# Ethernet.net
KiCad netlist of a schematic drawn in Altium Designer
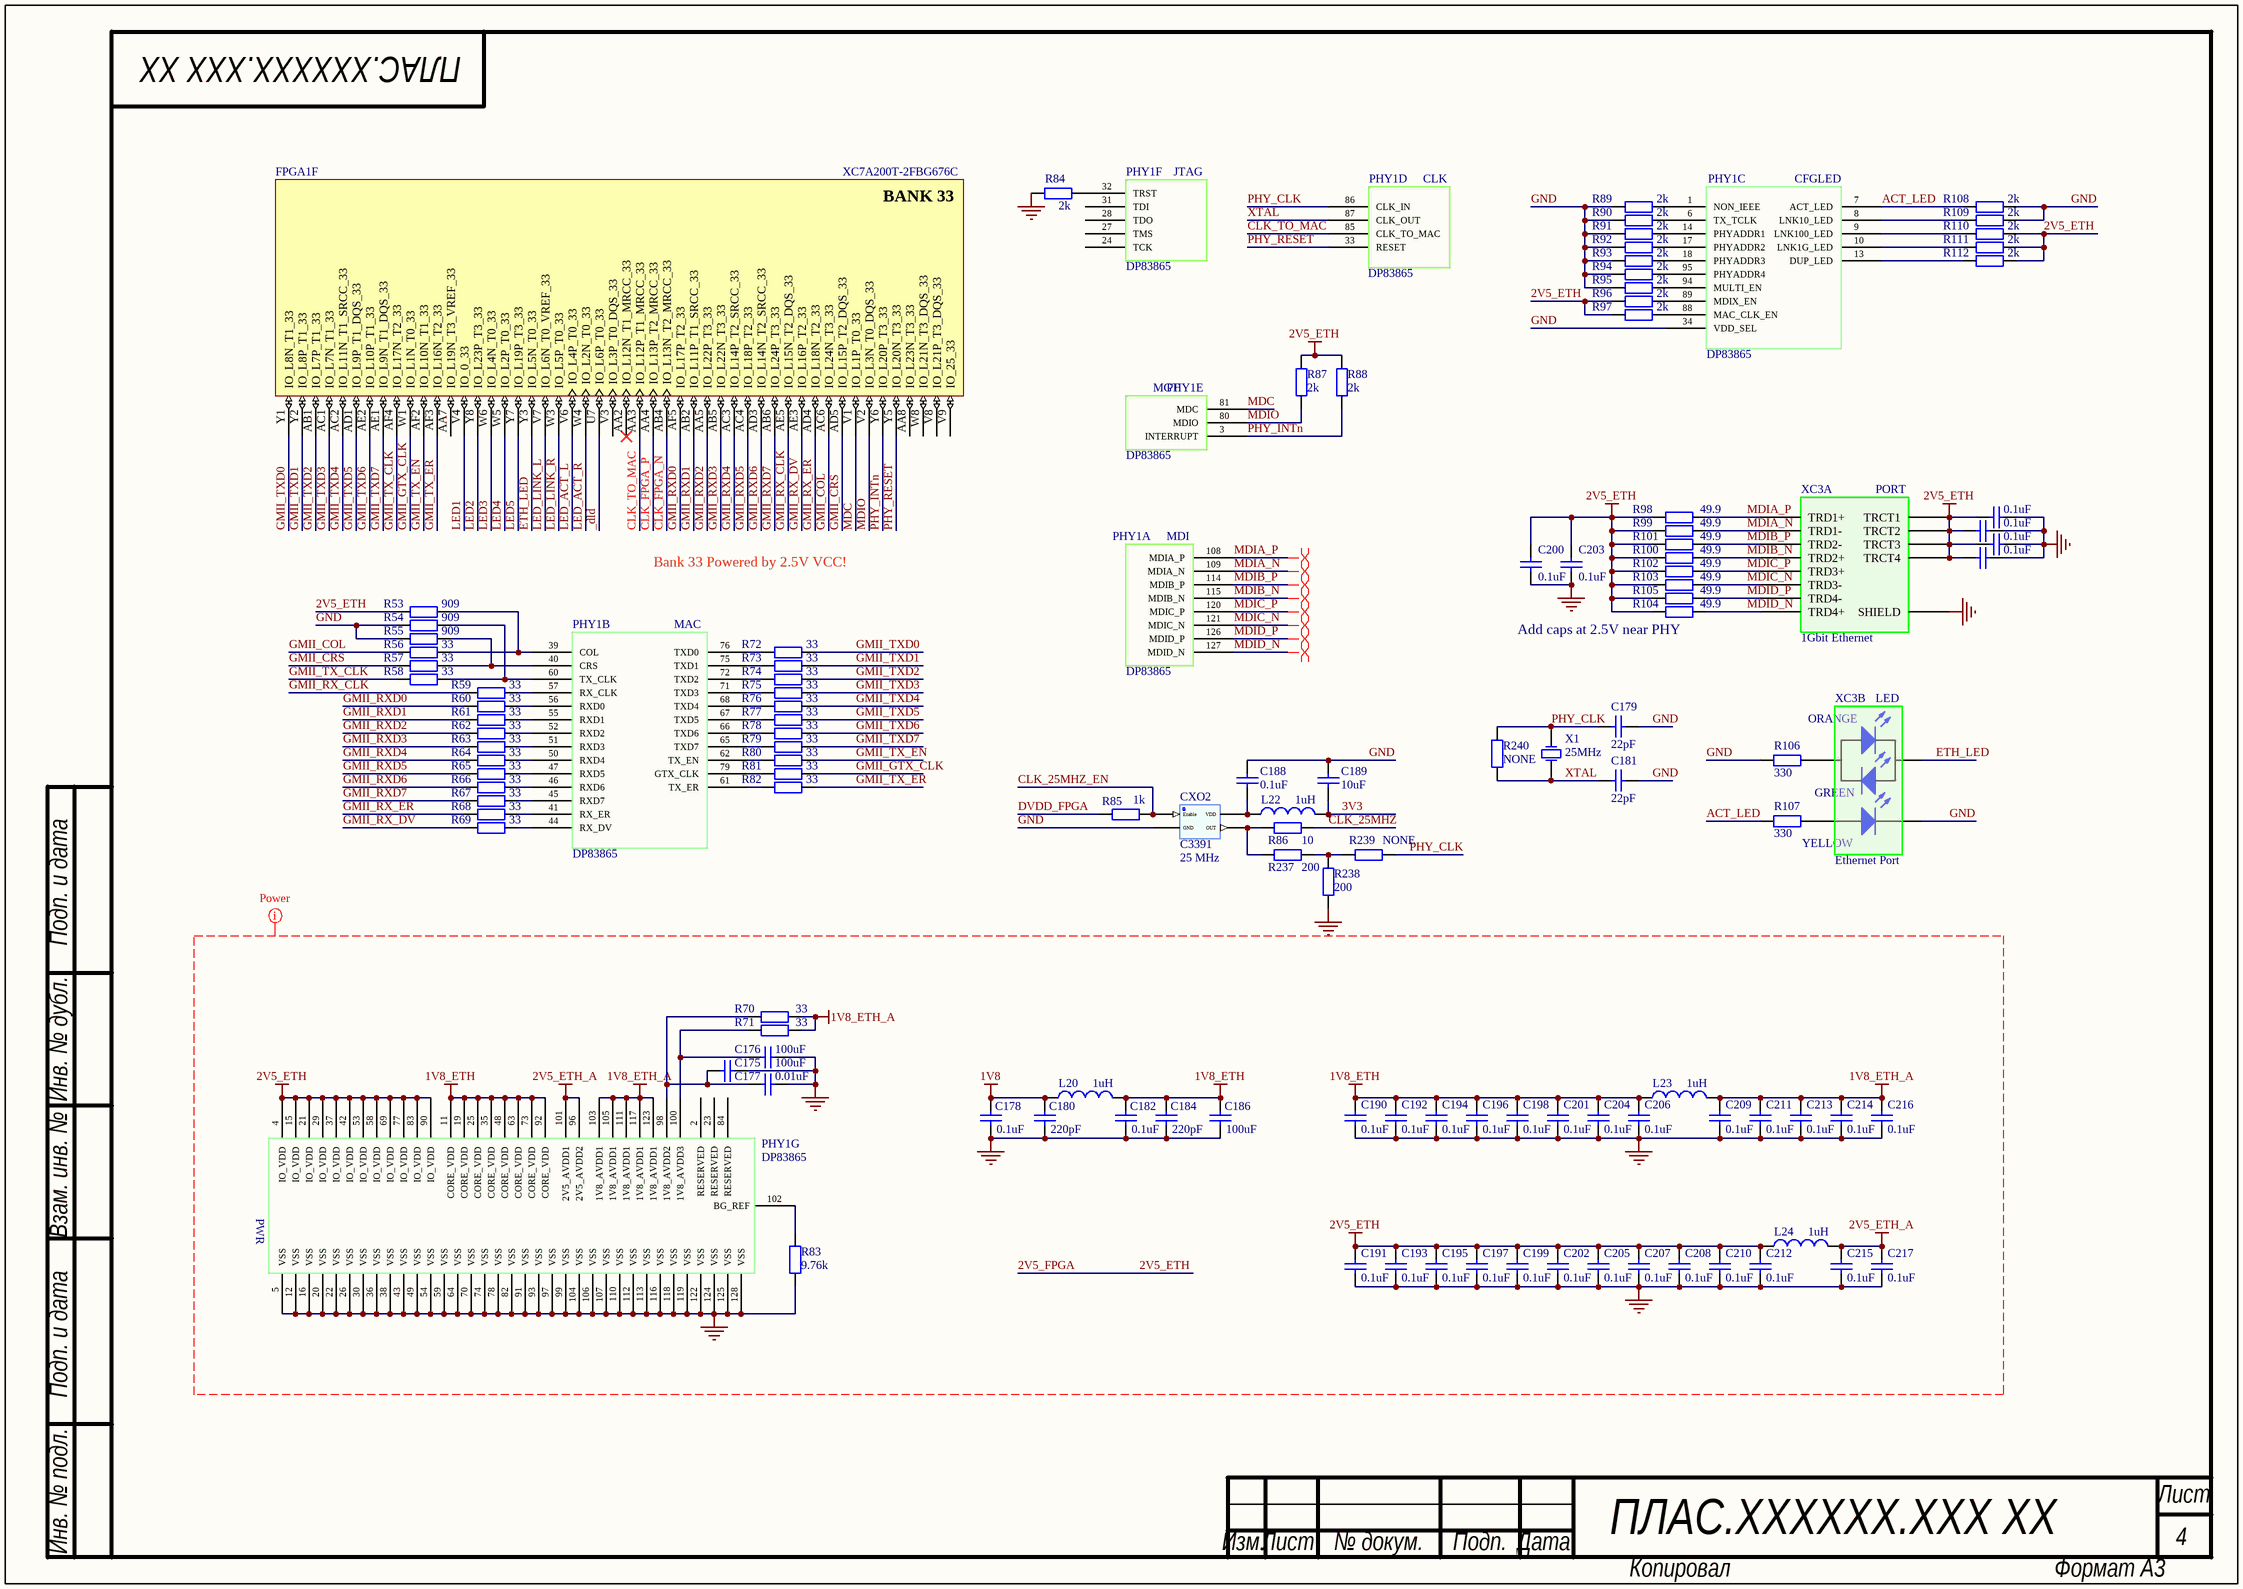
[diagram p0: Ethernet.SchDoc]

(export (version "E")
  (design (tool "Eeschema 10.0.6"))
  (components
    (comp (ref "C175")
      (value "100uF")
      (footprint "C1210")
      (description "Cer Cap Large")
      (fields (field (name "MANUFACTURER") "Murata") (field (name "TOLERANCE") "20%"))
      (libsource (lib "USRP2_Clone") (part "Cap uF"))
    )
    (comp (ref "C176")
      (value "100uF")
      (footprint "C1210")
      (description "Cer Cap Large")
      (fields (field (name "MANUFACTURER") "Murata") (field (name "TOLERANCE") "20%"))
      (libsource (lib "USRP2_Clone") (part "Cap uF"))
    )
    (comp (ref "C177")
      (value "0.01uF")
      (footprint "C0603")
      (description "Cer Cap Small")
      (fields (field (name "MANUFACTURER") "Murata") (field (name "VOLTAGE") "50V"))
      (libsource (lib "") (part "Cer Cap_1"))
    )
    (comp (ref "C178")
      (value "0.1uF")
      (footprint "C0603")
      (description "Cer Cap Small")
      (fields (field (name "MANUFACTURER") "Murata") (field (name "VOLTAGE") "16V"))
      (libsource (lib "USRP2_Clone") (part "Cer Cap"))
    )
    (comp (ref "C179")
      (value "22pF")
      (footprint "С0402")
      (description "Cer Cap Small")
      (fields (field (name "MANUFACTURER") "Murata") (field (name "VOLTAGE") "50V"))
      (libsource (lib "USRP2_Clone") (part "Cer Cap"))
    )
    (comp (ref "C180")
      (value "220pF")
      (footprint "C0603")
      (description "Cer Cap Small")
      (fields (field (name "MANUFACTURER") "Murata") (field (name "VOLTAGE") "16V"))
      (libsource (lib "USRP2_Clone") (part "Cer Cap"))
    )
    (comp (ref "C181")
      (value "22pF")
      (footprint "С0402")
      (description "Cer Cap Small")
      (fields (field (name "MANUFACTURER") "Murata") (field (name "VOLTAGE") "50V"))
      (libsource (lib "USRP2_Clone") (part "Cer Cap"))
    )
    (comp (ref "C182")
      (value "0.1uF")
      (footprint "C0603")
      (description "Cer Cap Small")
      (fields (field (name "MANUFACTURER") "Murata") (field (name "VOLTAGE") "16V"))
      (libsource (lib "USRP2_Clone") (part "Cer Cap"))
    )
    (comp (ref "C184")
      (value "220pF")
      (footprint "C0603")
      (description "Cer Cap Small")
      (fields (field (name "MANUFACTURER") "Murata") (field (name "VOLTAGE") "16V"))
      (libsource (lib "USRP2_Clone") (part "Cer Cap"))
    )
    (comp (ref "C186")
      (value "100uF")
      (footprint "C1210")
      (description "Cer Cap Large")
      (fields (field (name "MANUFACTURER") "Murata") (field (name "TOLERANCE") "20%"))
      (libsource (lib "") (part "Cap uF_1"))
    )
    (comp (ref "C188")
      (value "0.1uF")
      (footprint "C0603")
      (description "Cer Cap Small")
      (fields (field (name "MANUFACTURER") "Murata") (field (name "VOLTAGE") "16V"))
      (libsource (lib "") (part "Cer Cap_1"))
    )
    (comp (ref "C189")
      (value "10uF")
      (footprint "C0603")
      (description "Cer Cap Small")
      (fields (field (name "MANUFACTURER") "Murata") (field (name "VOLTAGE") "6.3V"))
      (libsource (lib "") (part "Cer Cap_1"))
    )
    (comp (ref "C190")
      (value "0.1uF")
      (footprint "C0603")
      (description "Cer Cap Small")
      (fields (field (name "MANUFACTURER") "Murata") (field (name "VOLTAGE") "16V"))
      (libsource (lib "") (part "Cer Cap_1"))
    )
    (comp (ref "C191")
      (value "0.1uF")
      (footprint "C0603")
      (description "Cer Cap Small")
      (fields (field (name "MANUFACTURER") "Murata") (field (name "VOLTAGE") "16V"))
      (libsource (lib "USRP2_Clone") (part "Cer Cap"))
    )
    (comp (ref "C192")
      (value "0.1uF")
      (footprint "C0603")
      (description "Cer Cap Small")
      (fields (field (name "MANUFACTURER") "Murata") (field (name "VOLTAGE") "16V"))
      (libsource (lib "USRP2_Clone") (part "Cer Cap"))
    )
    (comp (ref "C193")
      (value "0.1uF")
      (footprint "C0603")
      (description "Cer Cap Small")
      (fields (field (name "MANUFACTURER") "Murata") (field (name "VOLTAGE") "16V"))
      (libsource (lib "USRP2_Clone") (part "Cer Cap"))
    )
    (comp (ref "C194")
      (value "0.1uF")
      (footprint "C0603")
      (description "Cer Cap Small")
      (fields (field (name "MANUFACTURER") "Murata") (field (name "VOLTAGE") "16V"))
      (libsource (lib "USRP2_Clone") (part "Cer Cap"))
    )
    (comp (ref "C195")
      (value "0.1uF")
      (footprint "C0603")
      (description "Cer Cap Small")
      (fields (field (name "MANUFACTURER") "Murata") (field (name "VOLTAGE") "16V"))
      (libsource (lib "USRP2_Clone") (part "Cer Cap"))
    )
    (comp (ref "C196")
      (value "0.1uF")
      (footprint "C0603")
      (description "Cer Cap Small")
      (fields (field (name "MANUFACTURER") "Murata") (field (name "VOLTAGE") "16V"))
      (libsource (lib "") (part "Cer Cap_1"))
    )
    (comp (ref "C197")
      (value "0.1uF")
      (footprint "C0603")
      (description "Cer Cap Small")
      (fields (field (name "MANUFACTURER") "Murata") (field (name "VOLTAGE") "16V"))
      (libsource (lib "USRP2_Clone") (part "Cer Cap"))
    )
    (comp (ref "C198")
      (value "0.1uF")
      (footprint "C0603")
      (description "Cer Cap Small")
      (fields (field (name "MANUFACTURER") "Murata") (field (name "VOLTAGE") "16V"))
      (libsource (lib "USRP2_Clone") (part "Cer Cap"))
    )
    (comp (ref "C199")
      (value "0.1uF")
      (footprint "C0603")
      (description "Cer Cap Small")
      (fields (field (name "MANUFACTURER") "Murata") (field (name "VOLTAGE") "16V"))
      (libsource (lib "") (part "Cer Cap_1"))
    )
    (comp (ref "C200")
      (value "0.1uF")
      (footprint "С0402")
      (description "Cer Cap Small")
      (fields (field (name "MANUFACTURER") "Murata") (field (name "VOLTAGE") "16V"))
      (libsource (lib "") (part "Cer Cap_1"))
    )
    (comp (ref "C201")
      (value "0.1uF")
      (footprint "C0603")
      (description "Cer Cap Small")
      (fields (field (name "MANUFACTURER") "Murata") (field (name "VOLTAGE") "16V"))
      (libsource (lib "USRP2_Clone") (part "Cer Cap"))
    )
    (comp (ref "C202")
      (value "0.1uF")
      (footprint "C0603")
      (description "Cer Cap Small")
      (fields (field (name "MANUFACTURER") "Murata") (field (name "VOLTAGE") "16V"))
      (libsource (lib "") (part "Cer Cap_1"))
    )
    (comp (ref "C203")
      (value "0.1uF")
      (footprint "С0402")
      (description "Cer Cap Small")
      (fields (field (name "MANUFACTURER") "Murata") (field (name "VOLTAGE") "16V"))
      (libsource (lib "") (part "Cer Cap_1"))
    )
    (comp (ref "C204")
      (value "0.1uF")
      (footprint "C0603")
      (description "Cer Cap Small")
      (fields (field (name "MANUFACTURER") "Murata") (field (name "VOLTAGE") "16V"))
      (libsource (lib "USRP2_Clone") (part "Cer Cap"))
    )
    (comp (ref "C205")
      (value "0.1uF")
      (footprint "C0603")
      (description "Cer Cap Small")
      (fields (field (name "MANUFACTURER") "Murata") (field (name "VOLTAGE") "16V"))
      (libsource (lib "USRP2_Clone") (part "Cer Cap"))
    )
    (comp (ref "C206")
      (value "0.1uF")
      (footprint "C0603")
      (description "Cer Cap Small")
      (fields (field (name "MANUFACTURER") "Murata") (field (name "VOLTAGE") "16V"))
      (libsource (lib "USRP2_Clone") (part "Cer Cap"))
    )
    (comp (ref "C207")
      (value "0.1uF")
      (footprint "C0603")
      (description "Cer Cap Small")
      (fields (field (name "MANUFACTURER") "Murata") (field (name "VOLTAGE") "16V"))
      (libsource (lib "USRP2_Clone") (part "Cer Cap"))
    )
    (comp (ref "C208")
      (value "0.1uF")
      (footprint "C0603")
      (description "Cer Cap Small")
      (fields (field (name "MANUFACTURER") "Murata") (field (name "VOLTAGE") "16V"))
      (libsource (lib "USRP2_Clone") (part "Cer Cap"))
    )
    (comp (ref "C209")
      (value "0.1uF")
      (footprint "C0603")
      (description "Cer Cap Small")
      (fields (field (name "MANUFACTURER") "Murata") (field (name "VOLTAGE") "16V"))
      (libsource (lib "USRP2_Clone") (part "Cer Cap"))
    )
    (comp (ref "C210")
      (value "0.1uF")
      (footprint "C0603")
      (description "Cer Cap Small")
      (fields (field (name "MANUFACTURER") "Murata") (field (name "VOLTAGE") "16V"))
      (libsource (lib "USRP2_Clone") (part "Cer Cap"))
    )
    (comp (ref "C211")
      (value "0.1uF")
      (footprint "C0603")
      (description "Cer Cap Small")
      (fields (field (name "MANUFACTURER") "Murata") (field (name "VOLTAGE") "16V"))
      (libsource (lib "USRP2_Clone") (part "Cer Cap"))
    )
    (comp (ref "C212")
      (value "0.1uF")
      (footprint "C0603")
      (description "Cer Cap Small")
      (fields (field (name "MANUFACTURER") "Murata") (field (name "VOLTAGE") "16V"))
      (libsource (lib "USRP2_Clone") (part "Cer Cap"))
    )
    (comp (ref "C213")
      (value "0.1uF")
      (footprint "C0603")
      (description "Cer Cap Small")
      (fields (field (name "MANUFACTURER") "Murata") (field (name "VOLTAGE") "16V"))
      (libsource (lib "USRP2_Clone") (part "Cer Cap"))
    )
    (comp (ref "C214")
      (value "0.1uF")
      (footprint "C0603")
      (description "Cer Cap Small")
      (fields (field (name "MANUFACTURER") "Murata") (field (name "VOLTAGE") "16V"))
      (libsource (lib "USRP2_Clone") (part "Cer Cap"))
    )
    (comp (ref "C215")
      (value "0.1uF")
      (footprint "C0603")
      (description "Cer Cap Small")
      (fields (field (name "MANUFACTURER") "Murata") (field (name "VOLTAGE") "16V"))
      (libsource (lib "USRP2_Clone") (part "Cer Cap"))
    )
    (comp (ref "C216")
      (value "0.1uF")
      (footprint "C0603")
      (description "Cer Cap Small")
      (fields (field (name "MANUFACTURER") "Murata") (field (name "VOLTAGE") "16V"))
      (libsource (lib "USRP2_Clone") (part "Cer Cap"))
    )
    (comp (ref "C217")
      (value "0.1uF")
      (footprint "C0603")
      (description "Cer Cap Small")
      (fields (field (name "MANUFACTURER") "Murata") (field (name "VOLTAGE") "16V"))
      (libsource (lib "USRP2_Clone") (part "Cer Cap"))
    )
    (comp (ref "C218")
      (value "0.1uF")
      (footprint "С0402")
      (description "Cer Cap Small")
      (fields (field (name "MANUFACTURER") "Murata") (field (name "VOLTAGE") "50V"))
      (libsource (lib "USRP2_Clone") (part "Cer Cap"))
    )
    (comp (ref "C219")
      (value "0.1uF")
      (footprint "С0402")
      (description "Cer Cap Small")
      (fields (field (name "MANUFACTURER") "Murata") (field (name "VOLTAGE") "50V"))
      (libsource (lib "") (part "Cer Cap_1"))
    )
    (comp (ref "C220")
      (value "0.1uF")
      (footprint "С0402")
      (description "Cer Cap Small")
      (fields (field (name "MANUFACTURER") "Murata") (field (name "VOLTAGE") "50V"))
      (libsource (lib "USRP2_Clone") (part "Cer Cap"))
    )
    (comp (ref "C221")
      (value "0.1uF")
      (footprint "С0402")
      (description "Cer Cap Small")
      (fields (field (name "MANUFACTURER") "Murata") (field (name "VOLTAGE") "50V"))
      (libsource (lib "USRP2_Clone") (part "Cer Cap"))
    )
    (comp (ref "CXO2")
      (value "C3391")
      (footprint "CTS_CB3")
      (description "Crystal Oscillator")
      (fields
        (field (name "VOLTAGE") "3.3V ±0.3V")
        (field (name "MANUFACTURER") "Crystek")
        (field (name "FREQUENCY") "25 MHz")
      )
      (libsource (lib "USRP2_Clone") (part "5x7 CXO"))
    )
    (comp (ref "FPGA1")
      (value "XC7A200T-2FBG676C")
      (footprint "FGG676")
      (description "Artix-7 FPGA, 400 User I/Os, 8 GTP, 676-Ball BGA, Speed Grade 2, Commercial Grade, Pb-Free")
      (fields (field (name "GENERIC PART NUMBER") "XC7A200T") (field (name "MANUFACTURER") "Xilinx"))
      (libsource (lib "USRP2_Clone") (part "XC7A200T-2FBG676C"))
    )
    (comp (ref "L20")
      (value "1uH")
      (footprint "L1210_Murata LQH")
      (description "Inductor_Power_Lines")
      (fields (field (name "TOLERANCE") "5%") (field (name "MANUFACTURER") "Murata"))
      (libsource (lib "") (part "Inductor_LF_1"))
    )
    (comp (ref "L22")
      (value "1uH")
      (footprint "L1206_Murata")
      (description "Inductor_Power_Lines")
      (fields (field (name "TOLERANCE") "5%") (field (name "MANUFACTURER") "Murata"))
      (libsource (lib "") (part "Inductor_LF_1"))
    )
    (comp (ref "L23")
      (value "1uH")
      (footprint "L1210_Murata LQH")
      (description "Inductor_Power_Lines")
      (fields (field (name "TOLERANCE") "5%") (field (name "MANUFACTURER") "Murata"))
      (libsource (lib "USRP2_Clone") (part "Inductor_LF"))
    )
    (comp (ref "L24")
      (value "1uH")
      (footprint "L1210_Murata LQH")
      (description "Inductor_Power_Lines")
      (fields (field (name "TOLERANCE") "5%") (field (name "MANUFACTURER") "Murata"))
      (libsource (lib "USRP2_Clone") (part "Inductor_LF"))
    )
    (comp (ref "PHY1")
      (value "DP83865")
      (footprint "LQFP-128")
      (description "10/100/1000 Ethernet Physical Layer")
      (libsource (lib "USRP2_Clone") (part "DP83865"))
    )
    (comp (ref "R53")
      (value "909")
      (footprint "R0402")
      (description "Resistor")
      (fields (field (name "TOLERANCE") "5%") (field (name "POWER") "0.062 Wt"))
      (libsource (lib "") (part "Res_1"))
    )
    (comp (ref "R54")
      (value "909")
      (footprint "R0402")
      (description "Resistor")
      (fields (field (name "TOLERANCE") "5%") (field (name "POWER") "0.062 Wt"))
      (libsource (lib "") (part "Res_1"))
    )
    (comp (ref "R55")
      (value "909")
      (footprint "R0402")
      (description "Resistor")
      (fields (field (name "TOLERANCE") "5%") (field (name "POWER") "0.062 Wt"))
      (libsource (lib "") (part "Res_2"))
    )
    (comp (ref "R56")
      (value "33")
      (footprint "R0402")
      (description "Resistor")
      (fields (field (name "TOLERANCE") "5%") (field (name "POWER") "0.062 Wt"))
      (libsource (lib "") (part "Res_1"))
    )
    (comp (ref "R57")
      (value "33")
      (footprint "R0402")
      (description "Resistor")
      (fields (field (name "TOLERANCE") "5%") (field (name "POWER") "0.062 Wt"))
      (libsource (lib "") (part "Res_1"))
    )
    (comp (ref "R58")
      (value "33")
      (footprint "R0402")
      (description "Resistor")
      (fields (field (name "TOLERANCE") "5%") (field (name "POWER") "0.062 Wt"))
      (libsource (lib "") (part "Res_1"))
    )
    (comp (ref "R59")
      (value "33")
      (footprint "R0402")
      (description "Resistor")
      (fields (field (name "TOLERANCE") "5%") (field (name "POWER") "0.062 Wt"))
      (libsource (lib "") (part "Res_2"))
    )
    (comp (ref "R60")
      (value "33")
      (footprint "R0402")
      (description "Resistor")
      (fields (field (name "TOLERANCE") "5%") (field (name "POWER") "0.062 Wt"))
      (libsource (lib "") (part "Res_2"))
    )
    (comp (ref "R61")
      (value "33")
      (footprint "R0402")
      (description "Resistor")
      (fields (field (name "TOLERANCE") "5%") (field (name "POWER") "0.062 Wt"))
      (libsource (lib "") (part "Res_2"))
    )
    (comp (ref "R62")
      (value "33")
      (footprint "R0402")
      (description "Resistor")
      (fields (field (name "TOLERANCE") "5%") (field (name "POWER") "0.062 Wt"))
      (libsource (lib "") (part "Res_2"))
    )
    (comp (ref "R63")
      (value "33")
      (footprint "R0402")
      (description "Resistor")
      (fields (field (name "TOLERANCE") "5%") (field (name "POWER") "0.062 Wt"))
      (libsource (lib "") (part "Res_2"))
    )
    (comp (ref "R64")
      (value "33")
      (footprint "R0402")
      (description "Resistor")
      (fields (field (name "TOLERANCE") "5%") (field (name "POWER") "0.062 Wt"))
      (libsource (lib "") (part "Res_2"))
    )
    (comp (ref "R65")
      (value "33")
      (footprint "R0402")
      (description "Resistor")
      (fields (field (name "TOLERANCE") "5%") (field (name "POWER") "0.062 Wt"))
      (libsource (lib "") (part "Res_2"))
    )
    (comp (ref "R66")
      (value "33")
      (footprint "R0402")
      (description "Resistor")
      (fields (field (name "TOLERANCE") "5%") (field (name "POWER") "0.062 Wt"))
      (libsource (lib "") (part "Res_2"))
    )
    (comp (ref "R67")
      (value "33")
      (footprint "R0402")
      (description "Resistor")
      (fields (field (name "TOLERANCE") "5%") (field (name "POWER") "0.062 Wt"))
      (libsource (lib "") (part "Res_2"))
    )
    (comp (ref "R68")
      (value "33")
      (footprint "R0402")
      (description "Resistor")
      (fields (field (name "TOLERANCE") "5%") (field (name "POWER") "0.062 Wt"))
      (libsource (lib "") (part "Res_2"))
    )
    (comp (ref "R69")
      (value "33")
      (footprint "R0402")
      (description "Resistor")
      (fields (field (name "TOLERANCE") "5%") (field (name "POWER") "0.062 Wt"))
      (libsource (lib "") (part "Res_2"))
    )
    (comp (ref "R70")
      (value "33")
      (footprint "R0402")
      (description "Resistor")
      (fields (field (name "TOLERANCE") "5%") (field (name "POWER") "0.062 Wt"))
      (libsource (lib "USRP2_Clone") (part "Res"))
    )
    (comp (ref "R71")
      (value "33")
      (footprint "R0402")
      (description "Resistor")
      (fields (field (name "TOLERANCE") "5%") (field (name "POWER") "0.062 Wt"))
      (libsource (lib "USRP2_Clone") (part "Res"))
    )
    (comp (ref "R72")
      (value "33")
      (footprint "R0402")
      (description "Resistor")
      (fields (field (name "TOLERANCE") "5%") (field (name "POWER") "0.062 Wt"))
      (libsource (lib "") (part "Res_1"))
    )
    (comp (ref "R73")
      (value "33")
      (footprint "R0402")
      (description "Resistor")
      (fields (field (name "TOLERANCE") "5%") (field (name "POWER") "0.062 Wt"))
      (libsource (lib "") (part "Res_1"))
    )
    (comp (ref "R74")
      (value "33")
      (footprint "R0402")
      (description "Resistor")
      (fields (field (name "TOLERANCE") "5%") (field (name "POWER") "0.062 Wt"))
      (libsource (lib "") (part "Res_1"))
    )
    (comp (ref "R75")
      (value "33")
      (footprint "R0402")
      (description "Resistor")
      (fields (field (name "TOLERANCE") "5%") (field (name "POWER") "0.062 Wt"))
      (libsource (lib "") (part "Res_1"))
    )
    (comp (ref "R76")
      (value "33")
      (footprint "R0402")
      (description "Resistor")
      (fields (field (name "TOLERANCE") "5%") (field (name "POWER") "0.062 Wt"))
      (libsource (lib "") (part "Res_1"))
    )
    (comp (ref "R77")
      (value "33")
      (footprint "R0402")
      (description "Resistor")
      (fields (field (name "TOLERANCE") "5%") (field (name "POWER") "0.062 Wt"))
      (libsource (lib "") (part "Res_1"))
    )
    (comp (ref "R78")
      (value "33")
      (footprint "R0402")
      (description "Resistor")
      (fields (field (name "TOLERANCE") "5%") (field (name "POWER") "0.062 Wt"))
      (libsource (lib "") (part "Res_1"))
    )
    (comp (ref "R79")
      (value "33")
      (footprint "R0402")
      (description "Resistor")
      (fields (field (name "TOLERANCE") "5%") (field (name "POWER") "0.062 Wt"))
      (libsource (lib "") (part "Res_1"))
    )
    (comp (ref "R80")
      (value "33")
      (footprint "R0402")
      (description "Resistor")
      (fields (field (name "TOLERANCE") "5%") (field (name "POWER") "0.062 Wt"))
      (libsource (lib "") (part "Res_1"))
    )
    (comp (ref "R81")
      (value "33")
      (footprint "R0402")
      (description "Resistor")
      (fields (field (name "TOLERANCE") "5%") (field (name "POWER") "0.062 Wt"))
      (libsource (lib "") (part "Res_1"))
    )
    (comp (ref "R82")
      (value "33")
      (footprint "R0402")
      (description "Resistor")
      (fields (field (name "TOLERANCE") "5%") (field (name "POWER") "0.062 Wt"))
      (libsource (lib "") (part "Res_1"))
    )
    (comp (ref "R83")
      (value "9.76k")
      (footprint "R0402")
      (description "Resistor")
      (fields (field (name "TOLERANCE") "5%") (field (name "POWER") "0.062 Wt"))
      (libsource (lib "") (part "Res_4"))
    )
    (comp (ref "R84")
      (value "2k")
      (footprint "R0402")
      (description "Resistor")
      (fields (field (name "TOLERANCE") "5%") (field (name "POWER") "0.062 Wt"))
      (libsource (lib "") (part "Res_2"))
    )
    (comp (ref "R85")
      (value "1k")
      (footprint "R0402")
      (description "Resistor")
      (fields (field (name "TOLERANCE") "5%") (field (name "POWER") "0.062 Wt"))
      (libsource (lib "") (part "Res_2"))
    )
    (comp (ref "R86")
      (value "10")
      (footprint "R0402")
      (description "Resistor")
      (fields (field (name "TOLERANCE") "5%") (field (name "POWER") "0.062 Wt"))
      (libsource (lib "") (part "Res_2"))
    )
    (comp (ref "R87")
      (value "2k")
      (footprint "R0402")
      (description "Resistor")
      (fields (field (name "TOLERANCE") "5%") (field (name "POWER") "0.062 Wt"))
      (libsource (lib "") (part "Res_3"))
    )
    (comp (ref "R88")
      (value "2k")
      (footprint "R0402")
      (description "Resistor")
      (fields (field (name "TOLERANCE") "5%") (field (name "POWER") "0.062 Wt"))
      (libsource (lib "USRP2_Clone") (part "Res"))
    )
    (comp (ref "R89")
      (value "2k")
      (footprint "R0402")
      (description "Resistor")
      (fields (field (name "TOLERANCE") "5%") (field (name "POWER") "0.062 Wt"))
      (libsource (lib "") (part "Res_2"))
    )
    (comp (ref "R90")
      (value "2k")
      (footprint "R0402")
      (description "Resistor")
      (fields (field (name "TOLERANCE") "5%") (field (name "POWER") "0.062 Wt"))
      (libsource (lib "") (part "Res_2"))
    )
    (comp (ref "R91")
      (value "2k")
      (footprint "R0402")
      (description "Resistor")
      (fields (field (name "TOLERANCE") "5%") (field (name "POWER") "0.062 Wt"))
      (libsource (lib "") (part "Res_1"))
    )
    (comp (ref "R92")
      (value "2k")
      (footprint "R0402")
      (description "Resistor")
      (fields (field (name "TOLERANCE") "5%") (field (name "POWER") "0.062 Wt"))
      (libsource (lib "") (part "Res_2"))
    )
    (comp (ref "R93")
      (value "2k")
      (footprint "R0402")
      (description "Resistor")
      (fields (field (name "TOLERANCE") "5%") (field (name "POWER") "0.062 Wt"))
      (libsource (lib "") (part "Res_1"))
    )
    (comp (ref "R94")
      (value "2k")
      (footprint "R0402")
      (description "Resistor")
      (fields (field (name "TOLERANCE") "5%") (field (name "POWER") "0.062 Wt"))
      (libsource (lib "") (part "Res_1"))
    )
    (comp (ref "R95")
      (value "2k")
      (footprint "R0402")
      (description "Resistor")
      (fields (field (name "TOLERANCE") "5%") (field (name "POWER") "0.062 Wt"))
      (libsource (lib "") (part "Res_1"))
    )
    (comp (ref "R96")
      (value "2k")
      (footprint "R0402")
      (description "Resistor")
      (fields (field (name "TOLERANCE") "5%") (field (name "POWER") "0.062 Wt"))
      (libsource (lib "") (part "Res_1"))
    )
    (comp (ref "R97")
      (value "2k")
      (footprint "R0402")
      (description "Resistor")
      (fields (field (name "TOLERANCE") "5%") (field (name "POWER") "0.062 Wt"))
      (libsource (lib "") (part "Res_1"))
    )
    (comp (ref "R98")
      (value "49.9")
      (footprint "R0402")
      (description "Resistor")
      (fields (field (name "TOLERANCE") "5%") (field (name "POWER") "0.062 Wt"))
      (libsource (lib "") (part "Res_1"))
    )
    (comp (ref "R99")
      (value "49.9")
      (footprint "R0402")
      (description "Resistor")
      (fields (field (name "TOLERANCE") "5%") (field (name "POWER") "0.062 Wt"))
      (libsource (lib "") (part "Res_1"))
    )
    (comp (ref "R100")
      (value "49.9")
      (footprint "R0402")
      (description "Resistor")
      (fields (field (name "TOLERANCE") "5%") (field (name "POWER") "0.062 Wt"))
      (libsource (lib "") (part "Res_1"))
    )
    (comp (ref "R101")
      (value "49.9")
      (footprint "R0402")
      (description "Resistor")
      (fields (field (name "TOLERANCE") "5%") (field (name "POWER") "0.062 Wt"))
      (libsource (lib "") (part "Res_1"))
    )
    (comp (ref "R102")
      (value "49.9")
      (footprint "R0402")
      (description "Resistor")
      (fields (field (name "TOLERANCE") "5%") (field (name "POWER") "0.062 Wt"))
      (libsource (lib "") (part "Res_1"))
    )
    (comp (ref "R103")
      (value "49.9")
      (footprint "R0402")
      (description "Resistor")
      (fields (field (name "TOLERANCE") "5%") (field (name "POWER") "0.062 Wt"))
      (libsource (lib "") (part "Res_1"))
    )
    (comp (ref "R104")
      (value "49.9")
      (footprint "R0402")
      (description "Resistor")
      (fields (field (name "TOLERANCE") "5%") (field (name "POWER") "0.062 Wt"))
      (libsource (lib "") (part "Res_1"))
    )
    (comp (ref "R105")
      (value "49.9")
      (footprint "R0402")
      (description "Resistor")
      (fields (field (name "TOLERANCE") "5%") (field (name "POWER") "0.062 Wt"))
      (libsource (lib "") (part "Res_1"))
    )
    (comp (ref "R106")
      (value "330")
      (footprint "R0402")
      (description "Resistor")
      (fields (field (name "TOLERANCE") "5%") (field (name "POWER") "0.062 Wt"))
      (libsource (lib "") (part "Res_2"))
    )
    (comp (ref "R107")
      (value "330")
      (footprint "R0402")
      (description "Resistor")
      (fields (field (name "TOLERANCE") "5%") (field (name "POWER") "0.062 Wt"))
      (libsource (lib "") (part "Res_1"))
    )
    (comp (ref "R108")
      (value "2k")
      (footprint "R0402")
      (description "Resistor")
      (fields (field (name "TOLERANCE") "5%") (field (name "POWER") "0.062 Wt"))
      (libsource (lib "") (part "Res_2"))
    )
    (comp (ref "R109")
      (value "2k")
      (footprint "R0402")
      (description "Resistor")
      (fields (field (name "TOLERANCE") "5%") (field (name "POWER") "0.062 Wt"))
      (libsource (lib "") (part "Res_2"))
    )
    (comp (ref "R110")
      (value "2k")
      (footprint "R0402")
      (description "Resistor")
      (fields (field (name "TOLERANCE") "5%") (field (name "POWER") "0.062 Wt"))
      (libsource (lib "") (part "Res_1"))
    )
    (comp (ref "R111")
      (value "2k")
      (footprint "R0402")
      (description "Resistor")
      (fields (field (name "TOLERANCE") "5%") (field (name "POWER") "0.062 Wt"))
      (libsource (lib "") (part "Res_1"))
    )
    (comp (ref "R112")
      (value "2k")
      (footprint "R0402")
      (description "Resistor")
      (fields (field (name "TOLERANCE") "5%") (field (name "POWER") "0.062 Wt"))
      (libsource (lib "") (part "Res_1"))
    )
    (comp (ref "R237")
      (value "200")
      (footprint "R0402")
      (description "Resistor")
      (fields (field (name "TOLERANCE") "5%") (field (name "POWER") "0.062 Wt"))
      (libsource (lib "") (part "Res_1"))
    )
    (comp (ref "R238")
      (value "200")
      (footprint "R0402")
      (description "Resistor")
      (fields (field (name "TOLERANCE") "5%") (field (name "POWER") "0.062 Wt"))
      (libsource (lib "USRP2_Clone") (part "Res"))
    )
    (comp (ref "R239")
      (value "NONE")
      (footprint "R0402")
      (description "Resistor")
      (fields (field (name "TOLERANCE") "5%") (field (name "POWER") "0.062 Wt"))
      (libsource (lib "") (part "Res_2"))
    )
    (comp (ref "R240")
      (value "NONE")
      (footprint "R0402")
      (description "Resistor")
      (fields (field (name "TOLERANCE") "5%") (field (name "POWER") "0.062 Wt"))
      (libsource (lib "") (part "Res_3"))
    )
    (comp (ref "X1")
      (value "25MHz")
      (footprint "XTAL")
      (description "XTAL")
      (fields (field (name "MANUFACTURER") "GEYER ELECTRONIC"))
      (libsource (lib "USRP2_Clone") (part "XTAL"))
    )
    (comp (ref "XC3")
      (value "1Gbit Ethernet")
      (footprint "0826-1X1T-23-F")
      (description "Gigabit Single Port")
      (libsource (lib "USRP2_Clone") (part "0826-1X1T-23-F"))
    )
  )
  (nets
    (net (code "1") (name "/3V3") (class "Default")
      (node (ref "C189") (pin "2") (pinfunction "2_2") (pintype "passive"))
      (node (ref "L22") (pin "1") (pinfunction "1_1") (pintype "passive"))
    )
    (net (code "2") (name "/ACT_LED") (class "Default")
      (node (ref "PHY1") (pin "7") (pinfunction "ACT_LED_7") (pintype "passive"))
      (node (ref "R107") (pin "1") (pinfunction "1_1") (pintype "passive"))
      (node (ref "R108") (pin "2") (pinfunction "2_2") (pintype "passive"))
    )
    (net (code "3") (name "/CLK_25MHZ") (class "Default")
      (node (ref "R86") (pin "1") (pinfunction "1_1") (pintype "passive"))
    )
    (net (code "4") (name "/CLK_25MHZ_EN") (class "Default")
      (node (ref "CXO2") (pin "1") (pinfunction "Enable_1") (pintype "input"))
      (node (ref "R85") (pin "1") (pinfunction "1_1") (pintype "passive"))
    )
    (net (code "5") (name "/CLK_FPGA_N") (class "Default")
      (node (ref "FPGA1") (pin "AB4") (pinfunction "IO_L13N_T2_MRCC_33_AB4") (pintype "bidirectional"))
    )
    (net (code "6") (name "/CLK_FPGA_P") (class "Default")
      (node (ref "FPGA1") (pin "AA4") (pinfunction "IO_L13P_T2_MRCC_33_AA4") (pintype "bidirectional"))
    )
    (net (code "7") (name "/CLK_TO_MAC") (class "Default")
      (node (ref "FPGA1") (pin "AA3") (pinfunction "IO_L12P_T1_MRCC_33_AA3") (pintype "bidirectional"))
      (node (ref "PHY1") (pin "85") (pinfunction "CLK_TO_MAC_85") (pintype "passive"))
    )
    (net (code "8") (name "/DVDD_FPGA") (class "Default")
      (node (ref "R85") (pin "2") (pinfunction "2_2") (pintype "passive"))
    )
    (net (code "9") (name "/ETH_LED") (class "Default")
      (node (ref "FPGA1") (pin "Y3") (pinfunction "IO_L5N_T0_33_Y3") (pintype "bidirectional"))
      (node (ref "XC3") (pin "16") (pinfunction "LED2_16") (pintype "passive"))
    )
    (net (code "10") (name "/GMII_COL") (class "Default")
      (node (ref "FPGA1") (pin "AC6") (pinfunction "IO_L24N_T3_33_AC6") (pintype "bidirectional"))
      (node (ref "R56") (pin "1") (pinfunction "1_1") (pintype "passive"))
    )
    (net (code "11") (name "/GMII_CRS") (class "Default")
      (node (ref "FPGA1") (pin "AD5") (pinfunction "IO_L15P_T2_DQS_33_AD5") (pintype "bidirectional"))
      (node (ref "R57") (pin "1") (pinfunction "1_1") (pintype "passive"))
    )
    (net (code "12") (name "/GMII_GTX_CLK") (class "Default")
      (node (ref "FPGA1") (pin "W1") (pinfunction "IO_L1N_T0_33_W1") (pintype "bidirectional"))
      (node (ref "R81") (pin "2") (pinfunction "2_2") (pintype "passive"))
    )
    (net (code "13") (name "/GMII_RXD0") (class "Default")
      (node (ref "FPGA1") (pin "AF5") (pinfunction "IO_L17P_T2_33_AF5") (pintype "bidirectional"))
      (node (ref "R60") (pin "2") (pinfunction "2_2") (pintype "passive"))
    )
    (net (code "14") (name "/GMII_RXD1") (class "Default")
      (node (ref "FPGA1") (pin "AB2") (pinfunction "IO_L11P_T1_SRCC_33_AB2") (pintype "bidirectional"))
      (node (ref "R61") (pin "2") (pinfunction "2_2") (pintype "passive"))
    )
    (net (code "15") (name "/GMII_RXD2") (class "Default")
      (node (ref "FPGA1") (pin "AA5") (pinfunction "IO_L22P_T3_33_AA5") (pintype "bidirectional"))
      (node (ref "R62") (pin "2") (pinfunction "2_2") (pintype "passive"))
    )
    (net (code "16") (name "/GMII_RXD3") (class "Default")
      (node (ref "FPGA1") (pin "AB5") (pinfunction "IO_L22N_T3_33_AB5") (pintype "bidirectional"))
      (node (ref "R63") (pin "2") (pinfunction "2_2") (pintype "passive"))
    )
    (net (code "17") (name "/GMII_RXD4") (class "Default")
      (node (ref "FPGA1") (pin "AC3") (pinfunction "IO_L14P_T2_SRCC_33_AC3") (pintype "bidirectional"))
      (node (ref "R64") (pin "2") (pinfunction "2_2") (pintype "passive"))
    )
    (net (code "18") (name "/GMII_RXD5") (class "Default")
      (node (ref "FPGA1") (pin "AC4") (pinfunction "IO_L18P_T2_33_AC4") (pintype "bidirectional"))
      (node (ref "R65") (pin "2") (pinfunction "2_2") (pintype "passive"))
    )
    (net (code "19") (name "/GMII_RXD6") (class "Default")
      (node (ref "FPGA1") (pin "AD3") (pinfunction "IO_L14N_T2_SRCC_33_AD3") (pintype "bidirectional"))
      (node (ref "R66") (pin "2") (pinfunction "2_2") (pintype "passive"))
    )
    (net (code "20") (name "/GMII_RXD7") (class "Default")
      (node (ref "FPGA1") (pin "AB6") (pinfunction "IO_L24P_T3_33_AB6") (pintype "bidirectional"))
      (node (ref "R67") (pin "2") (pinfunction "2_2") (pintype "passive"))
    )
    (net (code "21") (name "/GMII_RX_CLK") (class "Default")
      (node (ref "FPGA1") (pin "AE5") (pinfunction "IO_L15N_T2_DQS_33_AE5") (pintype "bidirectional"))
      (node (ref "R59") (pin "2") (pinfunction "2_2") (pintype "passive"))
    )
    (net (code "22") (name "/GMII_RX_DV") (class "Default")
      (node (ref "FPGA1") (pin "AE3") (pinfunction "IO_L16P_T2_33_AE3") (pintype "bidirectional"))
      (node (ref "R69") (pin "2") (pinfunction "2_2") (pintype "passive"))
    )
    (net (code "23") (name "/GMII_RX_ER") (class "Default")
      (node (ref "FPGA1") (pin "AD4") (pinfunction "IO_L18N_T2_33_AD4") (pintype "bidirectional"))
      (node (ref "R68") (pin "2") (pinfunction "2_2") (pintype "passive"))
    )
    (net (code "24") (name "/GMII_TXD0") (class "Default")
      (node (ref "FPGA1") (pin "Y1") (pinfunction "IO_L8N_T1_33_Y1") (pintype "bidirectional"))
      (node (ref "R72") (pin "2") (pinfunction "2_2") (pintype "passive"))
    )
    (net (code "25") (name "/GMII_TXD1") (class "Default")
      (node (ref "FPGA1") (pin "Y2") (pinfunction "IO_L8P_T1_33_Y2") (pintype "bidirectional"))
      (node (ref "R73") (pin "2") (pinfunction "2_2") (pintype "passive"))
    )
    (net (code "26") (name "/GMII_TXD2") (class "Default")
      (node (ref "FPGA1") (pin "AB1") (pinfunction "IO_L7P_T1_33_AB1") (pintype "bidirectional"))
      (node (ref "R74") (pin "2") (pinfunction "2_2") (pintype "passive"))
    )
    (net (code "27") (name "/GMII_TXD3") (class "Default")
      (node (ref "FPGA1") (pin "AC1") (pinfunction "IO_L7N_T1_33_AC1") (pintype "bidirectional"))
      (node (ref "R75") (pin "2") (pinfunction "2_2") (pintype "passive"))
    )
    (net (code "28") (name "/GMII_TXD4") (class "Default")
      (node (ref "FPGA1") (pin "AC2") (pinfunction "IO_L11N_T1_SRCC_33_AC2") (pintype "bidirectional"))
      (node (ref "R76") (pin "2") (pinfunction "2_2") (pintype "passive"))
    )
    (net (code "29") (name "/GMII_TXD5") (class "Default")
      (node (ref "FPGA1") (pin "AD1") (pinfunction "IO_L9P_T1_DQS_33_AD1") (pintype "bidirectional"))
      (node (ref "R77") (pin "2") (pinfunction "2_2") (pintype "passive"))
    )
    (net (code "30") (name "/GMII_TXD6") (class "Default")
      (node (ref "FPGA1") (pin "AE2") (pinfunction "IO_L10P_T1_33_AE2") (pintype "bidirectional"))
      (node (ref "R78") (pin "2") (pinfunction "2_2") (pintype "passive"))
    )
    (net (code "31") (name "/GMII_TXD7") (class "Default")
      (node (ref "FPGA1") (pin "AE1") (pinfunction "IO_L9N_T1_DQS_33_AE1") (pintype "bidirectional"))
      (node (ref "R79") (pin "2") (pinfunction "2_2") (pintype "passive"))
    )
    (net (code "32") (name "/GMII_TX_CLK") (class "Default")
      (node (ref "FPGA1") (pin "AF4") (pinfunction "IO_L17N_T2_33_AF4") (pintype "bidirectional"))
      (node (ref "R58") (pin "1") (pinfunction "1_1") (pintype "passive"))
    )
    (net (code "33") (name "/GMII_TX_EN") (class "Default")
      (node (ref "FPGA1") (pin "AF2") (pinfunction "IO_L10N_T1_33_AF2") (pintype "bidirectional"))
      (node (ref "R80") (pin "2") (pinfunction "2_2") (pintype "passive"))
    )
    (net (code "34") (name "/GMII_TX_ER") (class "Default")
      (node (ref "FPGA1") (pin "AF3") (pinfunction "IO_L16N_T2_33_AF3") (pintype "bidirectional"))
      (node (ref "R82") (pin "2") (pinfunction "2_2") (pintype "passive"))
    )
    (net (code "35") (name "/LED1") (class "Default")
      (node (ref "FPGA1") (pin "V4") (pinfunction "IO_0_33_V4") (pintype "bidirectional"))
    )
    (net (code "36") (name "/LED2") (class "Default")
      (node (ref "FPGA1") (pin "Y8") (pinfunction "IO_L23P_T3_33_Y8") (pintype "bidirectional"))
    )
    (net (code "37") (name "/LED3") (class "Default")
      (node (ref "FPGA1") (pin "W6") (pinfunction "IO_L4N_T0_33_W6") (pintype "bidirectional"))
    )
    (net (code "38") (name "/LED4") (class "Default")
      (node (ref "FPGA1") (pin "W5") (pinfunction "IO_L2P_T0_33_W5") (pintype "bidirectional"))
    )
    (net (code "39") (name "/LED5") (class "Default")
      (node (ref "FPGA1") (pin "Y7") (pinfunction "IO_L19P_T3_33_Y7") (pintype "bidirectional"))
    )
    (net (code "40") (name "/LED_ACT_L") (class "Default")
      (node (ref "FPGA1") (pin "V6") (pinfunction "IO_L4P_T0_33_V6") (pintype "bidirectional"))
    )
    (net (code "41") (name "/LED_ACT_R") (class "Default")
      (node (ref "FPGA1") (pin "W4") (pinfunction "IO_L2N_T0_33_W4") (pintype "bidirectional"))
    )
    (net (code "42") (name "/LED_LINK_L") (class "Default")
      (node (ref "FPGA1") (pin "V7") (pinfunction "IO_L6N_T0_VREF_33_V7") (pintype "bidirectional"))
    )
    (net (code "43") (name "/LED_LINK_R") (class "Default")
      (node (ref "FPGA1") (pin "W3") (pinfunction "IO_L5P_T0_33_W3") (pintype "bidirectional"))
    )
    (net (code "44") (name "/MDC") (class "Default")
      (node (ref "FPGA1") (pin "V1") (pinfunction "IO_L1P_T0_33_V1") (pintype "bidirectional"))
      (node (ref "PHY1") (pin "81") (pinfunction "MDC_81") (pintype "passive"))
    )
    (net (code "45") (name "/MDIA_N") (class "Default")
      (node (ref "PHY1") (pin "109") (pinfunction "MDIA_N_109") (pintype "passive"))
      (node (ref "R99") (pin "2") (pinfunction "2_2") (pintype "passive"))
      (node (ref "XC3") (pin "10") (pinfunction "TRD1-_10") (pintype "passive"))
    )
    (net (code "46") (name "/MDIA_P") (class "Default")
      (node (ref "PHY1") (pin "108") (pinfunction "MDIA_P_108") (pintype "passive"))
      (node (ref "R98") (pin "2") (pinfunction "2_2") (pintype "passive"))
      (node (ref "XC3") (pin "11") (pinfunction "TRD1+_11") (pintype "passive"))
    )
    (net (code "47") (name "/MDIB_N") (class "Default")
      (node (ref "PHY1") (pin "115") (pinfunction "MDIB_N_115") (pintype "passive"))
      (node (ref "R100") (pin "2") (pinfunction "2_2") (pintype "passive"))
      (node (ref "XC3") (pin "4") (pinfunction "TRD2+_4") (pintype "passive"))
    )
    (net (code "48") (name "/MDIB_P") (class "Default")
      (node (ref "PHY1") (pin "114") (pinfunction "MDIB_P_114") (pintype "passive"))
      (node (ref "R101") (pin "2") (pinfunction "2_2") (pintype "passive"))
      (node (ref "XC3") (pin "5") (pinfunction "TRD2-_5") (pintype "passive"))
    )
    (net (code "49") (name "/MDIC_N") (class "Default")
      (node (ref "PHY1") (pin "121") (pinfunction "MDIC_N_121") (pintype "passive"))
      (node (ref "R103") (pin "2") (pinfunction "2_2") (pintype "passive"))
      (node (ref "XC3") (pin "2") (pinfunction "TRD3-_2") (pintype "passive"))
    )
    (net (code "50") (name "/MDIC_P") (class "Default")
      (node (ref "PHY1") (pin "120") (pinfunction "MDIC_P_120") (pintype "passive"))
      (node (ref "R102") (pin "2") (pinfunction "2_2") (pintype "passive"))
      (node (ref "XC3") (pin "3") (pinfunction "TRD3+_3") (pintype "passive"))
    )
    (net (code "51") (name "/MDID_N") (class "Default")
      (node (ref "PHY1") (pin "127") (pinfunction "MDID_N_127") (pintype "passive"))
      (node (ref "R104") (pin "2") (pinfunction "2_2") (pintype "passive"))
      (node (ref "XC3") (pin "8") (pinfunction "TRD4+_8") (pintype "passive"))
    )
    (net (code "52") (name "/MDID_P") (class "Default")
      (node (ref "PHY1") (pin "126") (pinfunction "MDID_P_126") (pintype "passive"))
      (node (ref "R105") (pin "2") (pinfunction "2_2") (pintype "passive"))
      (node (ref "XC3") (pin "9") (pinfunction "TRD4-_9") (pintype "passive"))
    )
    (net (code "53") (name "/MDIO") (class "Default")
      (node (ref "FPGA1") (pin "V2") (pinfunction "IO_L3N_T0_DQS_33_V2") (pintype "bidirectional"))
      (node (ref "PHY1") (pin "80") (pinfunction "MDIO_80") (pintype "passive"))
      (node (ref "R87") (pin "2") (pinfunction "2_2") (pintype "passive"))
    )
    (net (code "54") (name "/PHY_CLK") (class "Default")
      (node (ref "C179") (pin "1") (pinfunction "1_1") (pintype "passive"))
      (node (ref "PHY1") (pin "86") (pinfunction "CLK_IN_86") (pintype "passive"))
      (node (ref "R239") (pin "1") (pinfunction "1_1") (pintype "passive"))
      (node (ref "R240") (pin "1") (pinfunction "1_1") (pintype "passive"))
      (node (ref "X1") (pin "3") (pinfunction "OSC2_3") (pintype "passive"))
    )
    (net (code "55") (name "/PHY_INTn") (class "Default")
      (node (ref "FPGA1") (pin "Y6") (pinfunction "IO_L20P_T3_33_Y6") (pintype "bidirectional"))
      (node (ref "PHY1") (pin "3") (pinfunction "INTERRUPT_3") (pintype "passive"))
      (node (ref "R88") (pin "2") (pinfunction "2_2") (pintype "passive"))
    )
    (net (code "56") (name "/PHY_RESET") (class "Default")
      (node (ref "FPGA1") (pin "Y5") (pinfunction "IO_L20N_T3_33_Y5") (pintype "bidirectional"))
      (node (ref "PHY1") (pin "33") (pinfunction "RESET_33") (pintype "passive"))
    )
    (net (code "57") (name "/XTAL") (class "Default")
      (node (ref "C181") (pin "1") (pinfunction "1_1") (pintype "passive"))
      (node (ref "PHY1") (pin "87") (pinfunction "CLK_OUT_87") (pintype "passive"))
      (node (ref "R240") (pin "2") (pinfunction "2_2") (pintype "passive"))
      (node (ref "X1") (pin "1") (pinfunction "OSC1_1") (pintype "passive"))
    )
    (net (code "58") (name "/_dld") (class "Default")
      (node (ref "FPGA1") (pin "U7") (pinfunction "IO_L6P_T0_33_U7") (pintype "bidirectional"))
    )
    (net (code "59") (name "1V8") (class "Default")
      (node (ref "C178") (pin "1") (pinfunction "1_1") (pintype "passive"))
      (node (ref "C180") (pin "1") (pinfunction "1_1") (pintype "passive"))
      (node (ref "L20") (pin "2") (pinfunction "2_2") (pintype "passive"))
    )
    (net (code "60") (name "1V8_ETH") (class "Default")
      (node (ref "C182") (pin "1") (pinfunction "1_1") (pintype "passive"))
      (node (ref "C184") (pin "1") (pinfunction "1_1") (pintype "passive"))
      (node (ref "C186") (pin "1") (pinfunction "1_1") (pintype "passive"))
      (node (ref "C190") (pin "2") (pinfunction "2_2") (pintype "passive"))
      (node (ref "C192") (pin "1") (pinfunction "1_1") (pintype "passive"))
      (node (ref "C194") (pin "1") (pinfunction "1_1") (pintype "passive"))
      (node (ref "C196") (pin "2") (pinfunction "2_2") (pintype "passive"))
      (node (ref "C198") (pin "1") (pinfunction "1_1") (pintype "passive"))
      (node (ref "C201") (pin "1") (pinfunction "1_1") (pintype "passive"))
      (node (ref "C204") (pin "1") (pinfunction "1_1") (pintype "passive"))
      (node (ref "C206") (pin "1") (pinfunction "1_1") (pintype "passive"))
      (node (ref "L20") (pin "1") (pinfunction "1_1") (pintype "passive"))
      (node (ref "L23") (pin "1") (pinfunction "1_1") (pintype "passive"))
      (node (ref "PHY1") (pin "11") (pinfunction "CORE_VDD_11") (pintype "passive"))
      (node (ref "PHY1") (pin "19") (pinfunction "CORE_VDD_19") (pintype "passive"))
      (node (ref "PHY1") (pin "25") (pinfunction "CORE_VDD_25") (pintype "passive"))
      (node (ref "PHY1") (pin "35") (pinfunction "CORE_VDD_35") (pintype "passive"))
      (node (ref "PHY1") (pin "48") (pinfunction "CORE_VDD_48") (pintype "passive"))
      (node (ref "PHY1") (pin "63") (pinfunction "CORE_VDD_63") (pintype "passive"))
      (node (ref "PHY1") (pin "73") (pinfunction "CORE_VDD_73") (pintype "passive"))
      (node (ref "PHY1") (pin "92") (pinfunction "CORE_VDD_92") (pintype "passive"))
    )
    (net (code "61") (name "1V8_ETH_A") (class "Default")
      (node (ref "C209") (pin "1") (pinfunction "1_1") (pintype "passive"))
      (node (ref "C211") (pin "1") (pinfunction "1_1") (pintype "passive"))
      (node (ref "C213") (pin "1") (pinfunction "1_1") (pintype "passive"))
      (node (ref "C214") (pin "1") (pinfunction "1_1") (pintype "passive"))
      (node (ref "C216") (pin "1") (pinfunction "1_1") (pintype "passive"))
      (node (ref "L23") (pin "2") (pinfunction "2_2") (pintype "passive"))
      (node (ref "PHY1") (pin "103") (pinfunction "1V8_AVDD1_103") (pintype "passive"))
      (node (ref "PHY1") (pin "105") (pinfunction "1V8_AVDD1_105") (pintype "passive"))
      (node (ref "PHY1") (pin "111") (pinfunction "1V8_AVDD1_111") (pintype "passive"))
      (node (ref "PHY1") (pin "117") (pinfunction "1V8_AVDD1_117") (pintype "passive"))
      (node (ref "PHY1") (pin "123") (pinfunction "1V8_AVDD1_123") (pintype "passive"))
      (node (ref "R70") (pin "1") (pinfunction "1_1") (pintype "passive"))
      (node (ref "R71") (pin "1") (pinfunction "1_1") (pintype "passive"))
    )
    (net (code "62") (name "2V5_ETH") (class "Default")
      (node (ref "C191") (pin "1") (pinfunction "1_1") (pintype "passive"))
      (node (ref "C193") (pin "1") (pinfunction "1_1") (pintype "passive"))
      (node (ref "C195") (pin "1") (pinfunction "1_1") (pintype "passive"))
      (node (ref "C197") (pin "1") (pinfunction "1_1") (pintype "passive"))
      (node (ref "C199") (pin "2") (pinfunction "2_2") (pintype "passive"))
      (node (ref "C200") (pin "1") (pinfunction "1_1") (pintype "passive"))
      (node (ref "C202") (pin "2") (pinfunction "2_2") (pintype "passive"))
      (node (ref "C203") (pin "1") (pinfunction "1_1") (pintype "passive"))
      (node (ref "C205") (pin "1") (pinfunction "1_1") (pintype "passive"))
      (node (ref "C207") (pin "1") (pinfunction "1_1") (pintype "passive"))
      (node (ref "C208") (pin "1") (pinfunction "1_1") (pintype "passive"))
      (node (ref "C210") (pin "1") (pinfunction "1_1") (pintype "passive"))
      (node (ref "C212") (pin "1") (pinfunction "1_1") (pintype "passive"))
      (node (ref "C218") (pin "1") (pinfunction "1_1") (pintype "passive"))
      (node (ref "C219") (pin "1") (pinfunction "1_1") (pintype "passive"))
      (node (ref "C220") (pin "1") (pinfunction "1_1") (pintype "passive"))
      (node (ref "C221") (pin "1") (pinfunction "1_1") (pintype "passive"))
      (node (ref "L24") (pin "1") (pinfunction "1_1") (pintype "passive"))
      (node (ref "PHY1") (pin "15") (pinfunction "IO_VDD_15") (pintype "passive"))
      (node (ref "PHY1") (pin "21") (pinfunction "IO_VDD_21") (pintype "passive"))
      (node (ref "PHY1") (pin "29") (pinfunction "IO_VDD_29") (pintype "passive"))
      (node (ref "PHY1") (pin "37") (pinfunction "IO_VDD_37") (pintype "passive"))
      (node (ref "PHY1") (pin "4") (pinfunction "IO_VDD_4") (pintype "passive"))
      (node (ref "PHY1") (pin "42") (pinfunction "IO_VDD_42") (pintype "passive"))
      (node (ref "PHY1") (pin "53") (pinfunction "IO_VDD_53") (pintype "passive"))
      (node (ref "PHY1") (pin "58") (pinfunction "IO_VDD_58") (pintype "passive"))
      (node (ref "PHY1") (pin "69") (pinfunction "IO_VDD_69") (pintype "passive"))
      (node (ref "PHY1") (pin "77") (pinfunction "IO_VDD_77") (pintype "passive"))
      (node (ref "PHY1") (pin "83") (pinfunction "IO_VDD_83") (pintype "passive"))
      (node (ref "PHY1") (pin "90") (pinfunction "IO_VDD_90") (pintype "passive"))
      (node (ref "R100") (pin "1") (pinfunction "1_1") (pintype "passive"))
      (node (ref "R101") (pin "1") (pinfunction "1_1") (pintype "passive"))
      (node (ref "R102") (pin "1") (pinfunction "1_1") (pintype "passive"))
      (node (ref "R103") (pin "1") (pinfunction "1_1") (pintype "passive"))
      (node (ref "R104") (pin "1") (pinfunction "1_1") (pintype "passive"))
      (node (ref "R105") (pin "1") (pinfunction "1_1") (pintype "passive"))
      (node (ref "R110") (pin "2") (pinfunction "2_2") (pintype "passive"))
      (node (ref "R111") (pin "2") (pinfunction "2_2") (pintype "passive"))
      (node (ref "R112") (pin "2") (pinfunction "2_2") (pintype "passive"))
      (node (ref "R53") (pin "1") (pinfunction "1_1") (pintype "passive"))
      (node (ref "R87") (pin "1") (pinfunction "1_1") (pintype "passive"))
      (node (ref "R88") (pin "1") (pinfunction "1_1") (pintype "passive"))
      (node (ref "R96") (pin "1") (pinfunction "1_1") (pintype "passive"))
      (node (ref "R97") (pin "1") (pinfunction "1_1") (pintype "passive"))
      (node (ref "R98") (pin "1") (pinfunction "1_1") (pintype "passive"))
      (node (ref "R99") (pin "1") (pinfunction "1_1") (pintype "passive"))
      (node (ref "XC3") (pin "1") (pinfunction "TRCT3_1") (pintype "passive"))
      (node (ref "XC3") (pin "12") (pinfunction "TRCT1_12") (pintype "passive"))
      (node (ref "XC3") (pin "6") (pinfunction "TRCT2_6") (pintype "passive"))
      (node (ref "XC3") (pin "7") (pinfunction "TRCT4_7") (pintype "passive"))
    )
    (net (code "63") (name "2V5_ETH_A") (class "Default")
      (node (ref "C215") (pin "1") (pinfunction "1_1") (pintype "passive"))
      (node (ref "C217") (pin "1") (pinfunction "1_1") (pintype "passive"))
      (node (ref "L24") (pin "2") (pinfunction "2_2") (pintype "passive"))
      (node (ref "PHY1") (pin "101") (pinfunction "2V5_AVDD1_101") (pintype "passive"))
      (node (ref "PHY1") (pin "96") (pinfunction "2V5_AVDD2_96") (pintype "passive"))
    )
    (net (code "64") (name "GND") (class "Default")
      (node (ref "C175") (pin "1") (pinfunction "1_1") (pintype "passive"))
      (node (ref "C176") (pin "1") (pinfunction "1_1") (pintype "passive"))
      (node (ref "C177") (pin "1") (pinfunction "1_1") (pintype "passive"))
      (node (ref "C178") (pin "2") (pinfunction "2_2") (pintype "passive"))
      (node (ref "C179") (pin "2") (pinfunction "2_2") (pintype "passive"))
      (node (ref "C180") (pin "2") (pinfunction "2_2") (pintype "passive"))
      (node (ref "C181") (pin "2") (pinfunction "2_2") (pintype "passive"))
      (node (ref "C182") (pin "2") (pinfunction "2_2") (pintype "passive"))
      (node (ref "C184") (pin "2") (pinfunction "2_2") (pintype "passive"))
      (node (ref "C186") (pin "2") (pinfunction "2_2") (pintype "passive"))
      (node (ref "C188") (pin "2") (pinfunction "2_2") (pintype "passive"))
      (node (ref "C189") (pin "1") (pinfunction "1_1") (pintype "passive"))
      (node (ref "C190") (pin "1") (pinfunction "1_1") (pintype "passive"))
      (node (ref "C191") (pin "2") (pinfunction "2_2") (pintype "passive"))
      (node (ref "C192") (pin "2") (pinfunction "2_2") (pintype "passive"))
      (node (ref "C193") (pin "2") (pinfunction "2_2") (pintype "passive"))
      (node (ref "C194") (pin "2") (pinfunction "2_2") (pintype "passive"))
      (node (ref "C195") (pin "2") (pinfunction "2_2") (pintype "passive"))
      (node (ref "C196") (pin "1") (pinfunction "1_1") (pintype "passive"))
      (node (ref "C197") (pin "2") (pinfunction "2_2") (pintype "passive"))
      (node (ref "C198") (pin "2") (pinfunction "2_2") (pintype "passive"))
      (node (ref "C199") (pin "1") (pinfunction "1_1") (pintype "passive"))
      (node (ref "C200") (pin "2") (pinfunction "2_2") (pintype "passive"))
      (node (ref "C201") (pin "2") (pinfunction "2_2") (pintype "passive"))
      (node (ref "C202") (pin "1") (pinfunction "1_1") (pintype "passive"))
      (node (ref "C203") (pin "2") (pinfunction "2_2") (pintype "passive"))
      (node (ref "C204") (pin "2") (pinfunction "2_2") (pintype "passive"))
      (node (ref "C205") (pin "2") (pinfunction "2_2") (pintype "passive"))
      (node (ref "C206") (pin "2") (pinfunction "2_2") (pintype "passive"))
      (node (ref "C207") (pin "2") (pinfunction "2_2") (pintype "passive"))
      (node (ref "C208") (pin "2") (pinfunction "2_2") (pintype "passive"))
      (node (ref "C209") (pin "2") (pinfunction "2_2") (pintype "passive"))
      (node (ref "C210") (pin "2") (pinfunction "2_2") (pintype "passive"))
      (node (ref "C211") (pin "2") (pinfunction "2_2") (pintype "passive"))
      (node (ref "C212") (pin "2") (pinfunction "2_2") (pintype "passive"))
      (node (ref "C213") (pin "2") (pinfunction "2_2") (pintype "passive"))
      (node (ref "C214") (pin "2") (pinfunction "2_2") (pintype "passive"))
      (node (ref "C215") (pin "2") (pinfunction "2_2") (pintype "passive"))
      (node (ref "C216") (pin "2") (pinfunction "2_2") (pintype "passive"))
      (node (ref "C217") (pin "2") (pinfunction "2_2") (pintype "passive"))
      (node (ref "C218") (pin "2") (pinfunction "2_2") (pintype "passive"))
      (node (ref "C219") (pin "2") (pinfunction "2_2") (pintype "passive"))
      (node (ref "C220") (pin "2") (pinfunction "2_2") (pintype "passive"))
      (node (ref "C221") (pin "2") (pinfunction "2_2") (pintype "passive"))
      (node (ref "CXO2") (pin "2") (pinfunction "GND_2") (pintype "passive"))
      (node (ref "PHY1") (pin "104") (pinfunction "VSS_104") (pintype "passive"))
      (node (ref "PHY1") (pin "106") (pinfunction "VSS_106") (pintype "passive"))
      (node (ref "PHY1") (pin "107") (pinfunction "VSS_107") (pintype "passive"))
      (node (ref "PHY1") (pin "110") (pinfunction "VSS_110") (pintype "passive"))
      (node (ref "PHY1") (pin "112") (pinfunction "VSS_112") (pintype "passive"))
      (node (ref "PHY1") (pin "113") (pinfunction "VSS_113") (pintype "passive"))
      (node (ref "PHY1") (pin "116") (pinfunction "VSS_116") (pintype "passive"))
      (node (ref "PHY1") (pin "118") (pinfunction "VSS_118") (pintype "passive"))
      (node (ref "PHY1") (pin "119") (pinfunction "VSS_119") (pintype "passive"))
      (node (ref "PHY1") (pin "12") (pinfunction "VSS_12") (pintype "passive"))
      (node (ref "PHY1") (pin "122") (pinfunction "VSS_122") (pintype "passive"))
      (node (ref "PHY1") (pin "124") (pinfunction "VSS_124") (pintype "passive"))
      (node (ref "PHY1") (pin "125") (pinfunction "VSS_125") (pintype "passive"))
      (node (ref "PHY1") (pin "128") (pinfunction "VSS_128") (pintype "passive"))
      (node (ref "PHY1") (pin "16") (pinfunction "VSS_16") (pintype "passive"))
      (node (ref "PHY1") (pin "20") (pinfunction "VSS_20") (pintype "passive"))
      (node (ref "PHY1") (pin "22") (pinfunction "VSS_22") (pintype "passive"))
      (node (ref "PHY1") (pin "26") (pinfunction "VSS_26") (pintype "passive"))
      (node (ref "PHY1") (pin "30") (pinfunction "VSS_30") (pintype "passive"))
      (node (ref "PHY1") (pin "34") (pinfunction "VDD_SEL_34") (pintype "passive"))
      (node (ref "PHY1") (pin "36") (pinfunction "VSS_36") (pintype "passive"))
      (node (ref "PHY1") (pin "38") (pinfunction "VSS_38") (pintype "passive"))
      (node (ref "PHY1") (pin "43") (pinfunction "VSS_43") (pintype "passive"))
      (node (ref "PHY1") (pin "49") (pinfunction "VSS_49") (pintype "passive"))
      (node (ref "PHY1") (pin "5") (pinfunction "VSS_5") (pintype "passive"))
      (node (ref "PHY1") (pin "54") (pinfunction "VSS_54") (pintype "passive"))
      (node (ref "PHY1") (pin "59") (pinfunction "VSS_59") (pintype "passive"))
      (node (ref "PHY1") (pin "64") (pinfunction "VSS_64") (pintype "passive"))
      (node (ref "PHY1") (pin "70") (pinfunction "VSS_70") (pintype "passive"))
      (node (ref "PHY1") (pin "74") (pinfunction "VSS_74") (pintype "passive"))
      (node (ref "PHY1") (pin "78") (pinfunction "VSS_78") (pintype "passive"))
      (node (ref "PHY1") (pin "82") (pinfunction "VSS_82") (pintype "passive"))
      (node (ref "PHY1") (pin "91") (pinfunction "VSS_91") (pintype "passive"))
      (node (ref "PHY1") (pin "93") (pinfunction "VSS_93") (pintype "passive"))
      (node (ref "PHY1") (pin "97") (pinfunction "VSS_97") (pintype "passive"))
      (node (ref "PHY1") (pin "99") (pinfunction "VSS_99") (pintype "passive"))
      (node (ref "R106") (pin "2") (pinfunction "2_2") (pintype "passive"))
      (node (ref "R108") (pin "1") (pinfunction "1_1") (pintype "passive"))
      (node (ref "R109") (pin "1") (pinfunction "1_1") (pintype "passive"))
      (node (ref "R238") (pin "2") (pinfunction "2_2") (pintype "passive"))
      (node (ref "R54") (pin "1") (pinfunction "1_1") (pintype "passive"))
      (node (ref "R55") (pin "2") (pinfunction "2_2") (pintype "passive"))
      (node (ref "R83") (pin "2") (pinfunction "2_2") (pintype "passive"))
      (node (ref "R84") (pin "2") (pinfunction "2_2") (pintype "passive"))
      (node (ref "R89") (pin "2") (pinfunction "2_2") (pintype "passive"))
      (node (ref "R90") (pin "2") (pinfunction "2_2") (pintype "passive"))
      (node (ref "R91") (pin "1") (pinfunction "1_1") (pintype "passive"))
      (node (ref "R92") (pin "2") (pinfunction "2_2") (pintype "passive"))
      (node (ref "R93") (pin "1") (pinfunction "1_1") (pintype "passive"))
      (node (ref "R94") (pin "1") (pinfunction "1_1") (pintype "passive"))
      (node (ref "R95") (pin "1") (pinfunction "1_1") (pintype "passive"))
      (node (ref "XC3") (pin "0") (pinfunction "SHIELD_0") (pintype "passive"))
      (node (ref "XC3") (pin "13") (pinfunction "LED1_13") (pintype "passive"))
    )
    (net (code "65") (name "Net-(CXO2-OUT)") (class "Default")
      (node (ref "CXO2") (pin "3") (pinfunction "OUT_3") (pintype "output"))
      (node (ref "R237") (pin "1") (pinfunction "1_1") (pintype "passive"))
      (node (ref "R86") (pin "2") (pinfunction "2_2") (pintype "passive"))
    )
    (net (code "66") (name "Net-(CXO2-VDD)") (class "Default")
      (node (ref "C188") (pin "1") (pinfunction "1_1") (pintype "passive"))
      (node (ref "CXO2") (pin "4") (pinfunction "VDD_4") (pintype "passive"))
      (node (ref "L22") (pin "2") (pinfunction "2_2") (pintype "passive"))
    )
    (net (code "67") (name "Net-(PHY1B-COL)") (class "Default")
      (node (ref "PHY1") (pin "39") (pinfunction "COL_39") (pintype "passive"))
      (node (ref "R53") (pin "2") (pinfunction "2_2") (pintype "passive"))
      (node (ref "R56") (pin "2") (pinfunction "2_2") (pintype "passive"))
    )
    (net (code "68") (name "Net-(PHY1B-CRS)") (class "Default")
      (node (ref "PHY1") (pin "40") (pinfunction "CRS_40") (pintype "passive"))
      (node (ref "R55") (pin "1") (pinfunction "1_1") (pintype "passive"))
      (node (ref "R57") (pin "2") (pinfunction "2_2") (pintype "passive"))
    )
    (net (code "69") (name "Net-(PHY1B-GTX_CLK)") (class "Default")
      (node (ref "PHY1") (pin "79") (pinfunction "GTX_CLK_79") (pintype "passive"))
      (node (ref "R81") (pin "1") (pinfunction "1_1") (pintype "passive"))
    )
    (net (code "70") (name "Net-(PHY1B-RXD0)") (class "Default")
      (node (ref "PHY1") (pin "56") (pinfunction "RXD0_56") (pintype "passive"))
      (node (ref "R60") (pin "1") (pinfunction "1_1") (pintype "passive"))
    )
    (net (code "71") (name "Net-(PHY1B-RXD1)") (class "Default")
      (node (ref "PHY1") (pin "55") (pinfunction "RXD1_55") (pintype "passive"))
      (node (ref "R61") (pin "1") (pinfunction "1_1") (pintype "passive"))
    )
    (net (code "72") (name "Net-(PHY1B-RXD2)") (class "Default")
      (node (ref "PHY1") (pin "52") (pinfunction "RXD2_52") (pintype "passive"))
      (node (ref "R62") (pin "1") (pinfunction "1_1") (pintype "passive"))
    )
    (net (code "73") (name "Net-(PHY1B-RXD3)") (class "Default")
      (node (ref "PHY1") (pin "51") (pinfunction "RXD3_51") (pintype "passive"))
      (node (ref "R63") (pin "1") (pinfunction "1_1") (pintype "passive"))
    )
    (net (code "74") (name "Net-(PHY1B-RXD4)") (class "Default")
      (node (ref "PHY1") (pin "50") (pinfunction "RXD4_50") (pintype "passive"))
      (node (ref "R64") (pin "1") (pinfunction "1_1") (pintype "passive"))
    )
    (net (code "75") (name "Net-(PHY1B-RXD5)") (class "Default")
      (node (ref "PHY1") (pin "47") (pinfunction "RXD5_47") (pintype "passive"))
      (node (ref "R65") (pin "1") (pinfunction "1_1") (pintype "passive"))
    )
    (net (code "76") (name "Net-(PHY1B-RXD6)") (class "Default")
      (node (ref "PHY1") (pin "46") (pinfunction "RXD6_46") (pintype "passive"))
      (node (ref "R66") (pin "1") (pinfunction "1_1") (pintype "passive"))
    )
    (net (code "77") (name "Net-(PHY1B-RXD7)") (class "Default")
      (node (ref "PHY1") (pin "45") (pinfunction "RXD7_45") (pintype "passive"))
      (node (ref "R67") (pin "1") (pinfunction "1_1") (pintype "passive"))
    )
    (net (code "78") (name "Net-(PHY1B-RX_CLK)") (class "Default")
      (node (ref "PHY1") (pin "57") (pinfunction "RX_CLK_57") (pintype "passive"))
      (node (ref "R59") (pin "1") (pinfunction "1_1") (pintype "passive"))
    )
    (net (code "79") (name "Net-(PHY1B-RX_DV)") (class "Default")
      (node (ref "PHY1") (pin "44") (pinfunction "RX_DV_44") (pintype "passive"))
      (node (ref "R69") (pin "1") (pinfunction "1_1") (pintype "passive"))
    )
    (net (code "80") (name "Net-(PHY1B-RX_ER)") (class "Default")
      (node (ref "PHY1") (pin "41") (pinfunction "RX_ER_41") (pintype "passive"))
      (node (ref "R68") (pin "1") (pinfunction "1_1") (pintype "passive"))
    )
    (net (code "81") (name "Net-(PHY1B-TXD0)") (class "Default")
      (node (ref "PHY1") (pin "76") (pinfunction "TXD0_76") (pintype "passive"))
      (node (ref "R72") (pin "1") (pinfunction "1_1") (pintype "passive"))
    )
    (net (code "82") (name "Net-(PHY1B-TXD1)") (class "Default")
      (node (ref "PHY1") (pin "75") (pinfunction "TXD1_75") (pintype "passive"))
      (node (ref "R73") (pin "1") (pinfunction "1_1") (pintype "passive"))
    )
    (net (code "83") (name "Net-(PHY1B-TXD2)") (class "Default")
      (node (ref "PHY1") (pin "72") (pinfunction "TXD2_72") (pintype "passive"))
      (node (ref "R74") (pin "1") (pinfunction "1_1") (pintype "passive"))
    )
    (net (code "84") (name "Net-(PHY1B-TXD3)") (class "Default")
      (node (ref "PHY1") (pin "71") (pinfunction "TXD3_71") (pintype "passive"))
      (node (ref "R75") (pin "1") (pinfunction "1_1") (pintype "passive"))
    )
    (net (code "85") (name "Net-(PHY1B-TXD4)") (class "Default")
      (node (ref "PHY1") (pin "68") (pinfunction "TXD4_68") (pintype "passive"))
      (node (ref "R76") (pin "1") (pinfunction "1_1") (pintype "passive"))
    )
    (net (code "86") (name "Net-(PHY1B-TXD5)") (class "Default")
      (node (ref "PHY1") (pin "67") (pinfunction "TXD5_67") (pintype "passive"))
      (node (ref "R77") (pin "1") (pinfunction "1_1") (pintype "passive"))
    )
    (net (code "87") (name "Net-(PHY1B-TXD6)") (class "Default")
      (node (ref "PHY1") (pin "66") (pinfunction "TXD6_66") (pintype "passive"))
      (node (ref "R78") (pin "1") (pinfunction "1_1") (pintype "passive"))
    )
    (net (code "88") (name "Net-(PHY1B-TXD7)") (class "Default")
      (node (ref "PHY1") (pin "65") (pinfunction "TXD7_65") (pintype "passive"))
      (node (ref "R79") (pin "1") (pinfunction "1_1") (pintype "passive"))
    )
    (net (code "89") (name "Net-(PHY1B-TX_CLK)") (class "Default")
      (node (ref "PHY1") (pin "60") (pinfunction "TX_CLK_60") (pintype "passive"))
      (node (ref "R54") (pin "2") (pinfunction "2_2") (pintype "passive"))
      (node (ref "R58") (pin "2") (pinfunction "2_2") (pintype "passive"))
    )
    (net (code "90") (name "Net-(PHY1B-TX_EN)") (class "Default")
      (node (ref "PHY1") (pin "62") (pinfunction "TX_EN_62") (pintype "passive"))
      (node (ref "R80") (pin "1") (pinfunction "1_1") (pintype "passive"))
    )
    (net (code "91") (name "Net-(PHY1B-TX_ER)") (class "Default")
      (node (ref "PHY1") (pin "61") (pinfunction "TX_ER_61") (pintype "passive"))
      (node (ref "R82") (pin "1") (pinfunction "1_1") (pintype "passive"))
    )
    (net (code "92") (name "Net-(PHY1C-DUP_LED)") (class "Default")
      (node (ref "PHY1") (pin "13") (pinfunction "DUP_LED_13") (pintype "passive"))
      (node (ref "R112") (pin "1") (pinfunction "1_1") (pintype "passive"))
    )
    (net (code "93") (name "Net-(PHY1C-LNK1G_LED)") (class "Default")
      (node (ref "PHY1") (pin "10") (pinfunction "LNK1G_LED_10") (pintype "passive"))
      (node (ref "R111") (pin "1") (pinfunction "1_1") (pintype "passive"))
    )
    (net (code "94") (name "Net-(PHY1C-LNK10_LED)") (class "Default")
      (node (ref "PHY1") (pin "8") (pinfunction "LNK10_LED_8") (pintype "passive"))
      (node (ref "R109") (pin "2") (pinfunction "2_2") (pintype "passive"))
    )
    (net (code "95") (name "Net-(PHY1C-LNK100_LED)") (class "Default")
      (node (ref "PHY1") (pin "9") (pinfunction "LNK100_LED_9") (pintype "passive"))
      (node (ref "R110") (pin "1") (pinfunction "1_1") (pintype "passive"))
    )
    (net (code "96") (name "Net-(PHY1C-MAC_CLK_EN)") (class "Default")
      (node (ref "PHY1") (pin "88") (pinfunction "MAC_CLK_EN_88") (pintype "passive"))
      (node (ref "R97") (pin "2") (pinfunction "2_2") (pintype "passive"))
    )
    (net (code "97") (name "Net-(PHY1C-MDIX_EN)") (class "Default")
      (node (ref "PHY1") (pin "89") (pinfunction "MDIX_EN_89") (pintype "passive"))
      (node (ref "R96") (pin "2") (pinfunction "2_2") (pintype "passive"))
    )
    (net (code "98") (name "Net-(PHY1C-MULTI_EN)") (class "Default")
      (node (ref "PHY1") (pin "94") (pinfunction "MULTI_EN_94") (pintype "passive"))
      (node (ref "R95") (pin "2") (pinfunction "2_2") (pintype "passive"))
    )
    (net (code "99") (name "Net-(PHY1C-NON_IEEE)") (class "Default")
      (node (ref "PHY1") (pin "1") (pinfunction "NON_IEEE_1") (pintype "passive"))
      (node (ref "R89") (pin "1") (pinfunction "1_1") (pintype "passive"))
    )
    (net (code "100") (name "Net-(PHY1C-PHYADDR1)") (class "Default")
      (node (ref "PHY1") (pin "14") (pinfunction "PHYADDR1_14") (pintype "passive"))
      (node (ref "R91") (pin "2") (pinfunction "2_2") (pintype "passive"))
    )
    (net (code "101") (name "Net-(PHY1C-PHYADDR2)") (class "Default")
      (node (ref "PHY1") (pin "17") (pinfunction "PHYADDR2_17") (pintype "passive"))
      (node (ref "R92") (pin "1") (pinfunction "1_1") (pintype "passive"))
    )
    (net (code "102") (name "Net-(PHY1C-PHYADDR3)") (class "Default")
      (node (ref "PHY1") (pin "18") (pinfunction "PHYADDR3_18") (pintype "passive"))
      (node (ref "R93") (pin "2") (pinfunction "2_2") (pintype "passive"))
    )
    (net (code "103") (name "Net-(PHY1C-PHYADDR4)") (class "Default")
      (node (ref "PHY1") (pin "95") (pinfunction "PHYADDR4_95") (pintype "passive"))
      (node (ref "R94") (pin "2") (pinfunction "2_2") (pintype "passive"))
    )
    (net (code "104") (name "Net-(PHY1C-TX_TCLK)") (class "Default")
      (node (ref "PHY1") (pin "6") (pinfunction "TX_TCLK_6") (pintype "passive"))
      (node (ref "R90") (pin "1") (pinfunction "1_1") (pintype "passive"))
    )
    (net (code "105") (name "Net-(PHY1F-TRST)") (class "Default")
      (node (ref "PHY1") (pin "32") (pinfunction "TRST_32") (pintype "passive"))
      (node (ref "R84") (pin "1") (pinfunction "1_1") (pintype "passive"))
    )
    (net (code "106") (name "Net-(PHY1G-1V8_AVDD2)") (class "Default")
      (node (ref "C175") (pin "2") (pinfunction "2_2") (pintype "passive"))
      (node (ref "C177") (pin "2") (pinfunction "2_2") (pintype "passive"))
      (node (ref "PHY1") (pin "98") (pinfunction "1V8_AVDD2_98") (pintype "passive"))
      (node (ref "R70") (pin "2") (pinfunction "2_2") (pintype "passive"))
    )
    (net (code "107") (name "Net-(PHY1G-1V8_AVDD3)") (class "Default")
      (node (ref "C176") (pin "2") (pinfunction "2_2") (pintype "passive"))
      (node (ref "PHY1") (pin "100") (pinfunction "1V8_AVDD3_100") (pintype "passive"))
      (node (ref "R71") (pin "2") (pinfunction "2_2") (pintype "passive"))
    )
    (net (code "108") (name "Net-(PHY1G-BG_REF)") (class "Default")
      (node (ref "PHY1") (pin "102") (pinfunction "BG_REF_102") (pintype "passive"))
      (node (ref "R83") (pin "1") (pinfunction "1_1") (pintype "passive"))
    )
    (net (code "109") (name "Net-(R106-Pad1)") (class "Default")
      (node (ref "R106") (pin "1") (pinfunction "1_1") (pintype "passive"))
      (node (ref "XC3") (pin "15") (pinfunction "15_15") (pintype "passive"))
    )
    (net (code "110") (name "Net-(R107-Pad2)") (class "Default")
      (node (ref "R107") (pin "2") (pinfunction "2_2") (pintype "passive"))
      (node (ref "XC3") (pin "14") (pinfunction "14_14") (pintype "passive"))
    )
    (net (code "111") (name "Net-(R237-Pad2)") (class "Default")
      (node (ref "R237") (pin "2") (pinfunction "2_2") (pintype "passive"))
      (node (ref "R238") (pin "1") (pinfunction "1_1") (pintype "passive"))
      (node (ref "R239") (pin "2") (pinfunction "2_2") (pintype "passive"))
    )
    (net (code "112") (name "unconnected-(FPGA1F-IO_25_33-PadV9)") (class "Default")
      (node (ref "FPGA1") (pin "V9") (pinfunction "IO_25_33_V9") (pintype "bidirectional"))
    )
    (net (code "113") (name "unconnected-(FPGA1F-IO_L3P_T0_DQS_33-PadV3)") (class "Default")
      (node (ref "FPGA1") (pin "V3") (pinfunction "IO_L3P_T0_DQS_33_V3") (pintype "bidirectional"))
    )
    (net (code "114") (name "unconnected-(FPGA1F-IO_L12N_T1_MRCC_33-PadAA2)") (class "Default")
      (node (ref "FPGA1") (pin "AA2") (pinfunction "IO_L12N_T1_MRCC_33_AA2") (pintype "bidirectional+no_connect"))
    )
    (net (code "115") (name "unconnected-(FPGA1F-IO_L19N_T3_VREF_33-PadAA7)") (class "Default")
      (node (ref "FPGA1") (pin "AA7") (pinfunction "IO_L19N_T3_VREF_33_AA7") (pintype "bidirectional"))
    )
    (net (code "116") (name "unconnected-(FPGA1F-IO_L21N_T3_DQS_33-PadW8)") (class "Default")
      (node (ref "FPGA1") (pin "W8") (pinfunction "IO_L21N_T3_DQS_33_W8") (pintype "bidirectional"))
    )
    (net (code "117") (name "unconnected-(FPGA1F-IO_L21P_T3_DQS_33-PadV8)") (class "Default")
      (node (ref "FPGA1") (pin "V8") (pinfunction "IO_L21P_T3_DQS_33_V8") (pintype "bidirectional"))
    )
    (net (code "118") (name "unconnected-(FPGA1F-IO_L23N_T3_33-PadAA8)") (class "Default")
      (node (ref "FPGA1") (pin "AA8") (pinfunction "IO_L23N_T3_33_AA8") (pintype "bidirectional"))
    )
    (net (code "119") (name "unconnected-(PHY1F-TCK-Pad24)") (class "Default")
      (node (ref "PHY1") (pin "24") (pinfunction "TCK_24") (pintype "passive"))
    )
    (net (code "120") (name "unconnected-(PHY1F-TDI-Pad31)") (class "Default")
      (node (ref "PHY1") (pin "31") (pinfunction "TDI_31") (pintype "passive"))
    )
    (net (code "121") (name "unconnected-(PHY1F-TDO-Pad28)") (class "Default")
      (node (ref "PHY1") (pin "28") (pinfunction "TDO_28") (pintype "passive"))
    )
    (net (code "122") (name "unconnected-(PHY1F-TMS-Pad27)") (class "Default")
      (node (ref "PHY1") (pin "27") (pinfunction "TMS_27") (pintype "passive"))
    )
    (net (code "123") (name "unconnected-(PHY1G-RESERVED-Pad2)") (class "Default")
      (node (ref "PHY1") (pin "2") (pinfunction "RESERVED_2") (pintype "passive"))
    )
    (net (code "124") (name "unconnected-(PHY1G-RESERVED-Pad23)") (class "Default")
      (node (ref "PHY1") (pin "23") (pinfunction "RESERVED_23") (pintype "passive"))
    )
    (net (code "125") (name "unconnected-(PHY1G-RESERVED-Pad84)") (class "Default")
      (node (ref "PHY1") (pin "84") (pinfunction "RESERVED_84") (pintype "passive"))
    )
  )
)
